# OPTICS.net
KiCad netlist of a schematic drawn in Altium Designer
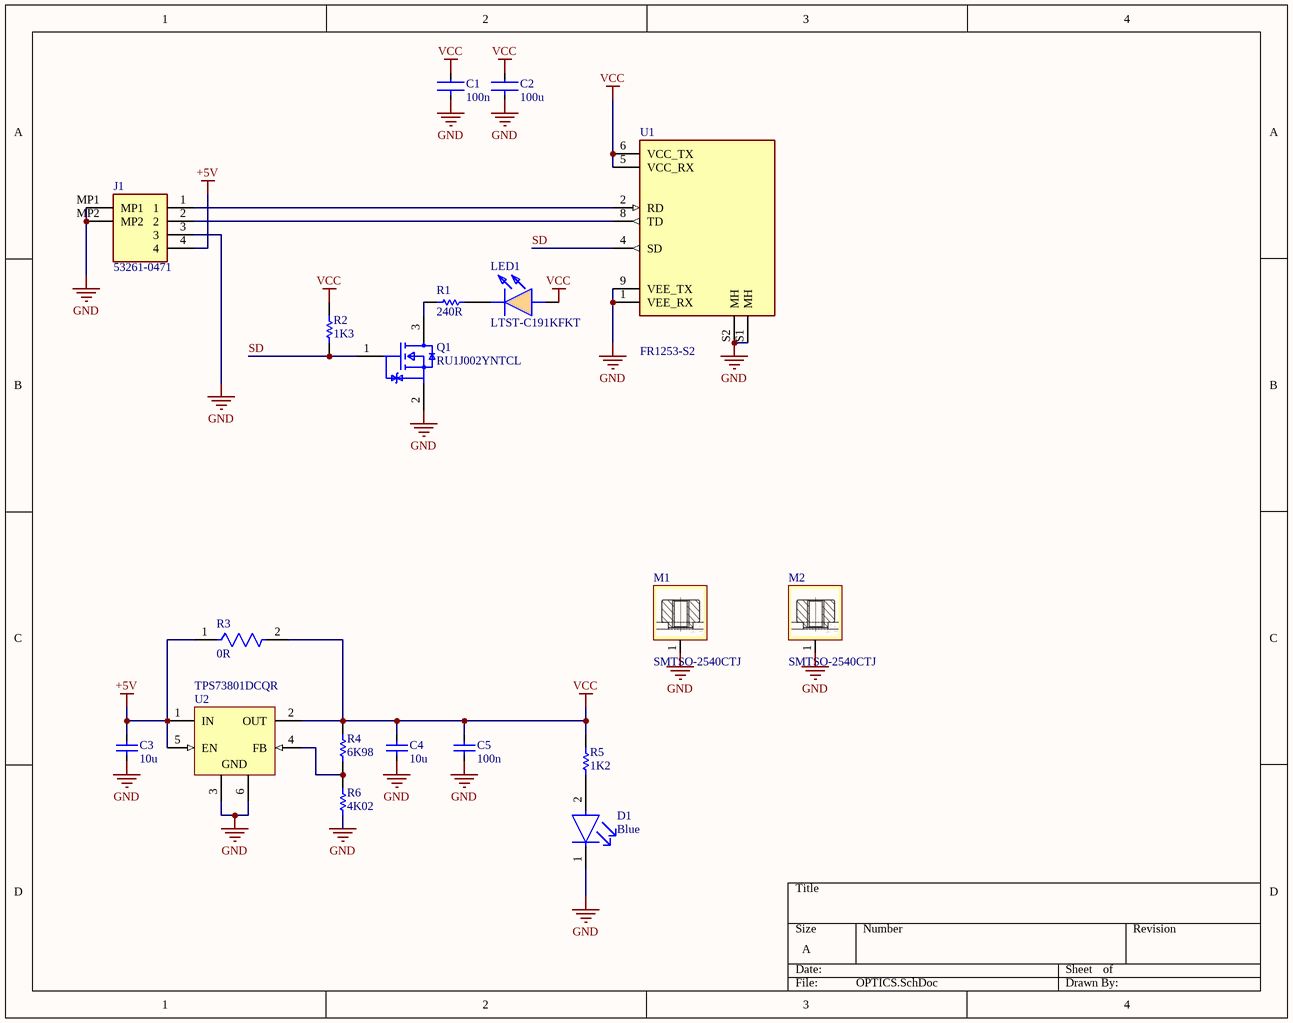
[diagram p0: OPTICS.SchDoc]

(export (version "E")
  (design (tool "Eeschema 10.0.6"))
  (components
    (comp (ref "C1")
      (value "100n")
      (footprint "FP-C1005-050-0_05-IPC_B")
      (description "Multilayer Ceramic Capacitors 100nF ±10% 50V X7R SMD 0402")
      (fields (field (name "VOLTAGE") "50V") (field (name "TOLERANCE") "10%"))
      (libsource (lib "Altium Content Vault") (part "b4654b650e69147ec39a6b967a45e02"))
    )
    (comp (ref "C2")
      (value "100u")
      (footprint "FP-C3216-160-0_3-IPC_B")
      (description "Multilayer Ceramic Capacitors 100uF ±20% 4V X5R SMD 1206")
      (fields (field (name "TOLERANCE") "20%") (field (name "PART NUMBER") "C3216X5R0G107M160AB"))
      (libsource (lib "Altium Content Vault") (part "02cd4be3c70576c341d710602a673aa"))
    )
    (comp (ref "C3")
      (value "10u")
      (footprint "FP-C1608-080-0_1-IPC_C")
      (description "MLCC 10μF ±10% 6.3V JB SMD 0603")
      (fields (field (name "TOLERANCE") "10%") (field (name "Comment") "C1608JB0J106K080AB"))
      (libsource (lib "Schlib1") (part "C1608JB0J106K080AB"))
    )
    (comp (ref "C4")
      (value "10u")
      (footprint "FP-C1608-080-0_1-IPC_C")
      (description "MLCC 10μF ±10% 6.3V JB SMD 0603")
      (fields (field (name "TOLERANCE") "10%") (field (name "Comment") "C1608JB0J106K080AB"))
      (libsource (lib "Schlib1") (part "C1608JB0J106K080AB"))
    )
    (comp (ref "C5")
      (value "100n")
      (footprint "FP-C1005-050-0_05-IPC_C")
      (description "MLCC 100nF ±10% 50V X7R SMD 0402")
      (fields (field (name "VOLTAGE") "50V") (field (name "TOLERANCE") "10%"))
      (libsource (lib "Schlib1") (part "C1005X7R1H104K050BB"))
    )
    (comp (ref "D1")
      (value "LTST-C191TBKT")
      (footprint "FP-LTST-C191TBKT-MFG")
      (description "LED BLUE CLEAR CHIP SMD")
      (fields (field (name "COLOR") "Blue"))
      (libsource (lib "Altium Content Vault") (part "8706943c75ba83719d021d2fdc84c58"))
    )
    (comp (ref "J1")
      (value "53261-0471")
      (footprint "SamacSys:53261-0471")
      (description "Connector")
      (fields (field (name "MOUSER PART NUMBER") "538-53261-0471"))
      (libsource (lib "SamacSys") (part "53261-0471"))
    )
    (comp (ref "LED1")
      (value "LTST-C191KFKT")
      (footprint "SamacSys:LEDC1608X55N")
      (description "LED")
      (fields (field (name "MOUSER PART NUMBER") "859-LTST-C191KFKT") (field (name "MANUFACTURER") "Lite-On"))
      (libsource (lib "SamacSys") (part "LTST-C191KFKT"))
    )
    (comp (ref "M1")
      (value "SMTSO-2540CTJ")
      (footprint "SMTSO-2540CTJ")
      (libsource (lib "Schlib1") (part "SMTSO-2540CTJ"))
    )
    (comp (ref "M2")
      (value "SMTSO-2540CTJ")
      (footprint "SMTSO-2540CTJ")
      (libsource (lib "Schlib1") (part "SMTSO-2540CTJ"))
    )
    (comp (ref "Q1")
      (value "RU1J002YNTCL")
      (footprint "FP-UMT3F-MFG")
      (description "MOSFET N-CH 50V 0.2A UMT3F")
      (fields
        (field (name "MANUFACTURER") "Rohm")
        (field (name "OCTOPART") "https://octopart.com/ru1j002yntcl-rohm-47197697")
      )
      (libsource (lib "Schlib1") (part "RU1J002YNTCL"))
    )
    (comp (ref "R1")
      (value "240R")
      (footprint "RESC0402(1005)_M")
      (description "240R 0.063W 1% 0402 (1005 Metric)  SMD")
      (fields (field (name "POWER") "0.063 W") (field (name "TOLERANCE") "1 %"))
      (libsource (lib "Altium Content Vault") (part "RES"))
    )
    (comp (ref "R2")
      (value "1K3")
      (footprint "RESC1005X40X25ML05T10")
      (fields (field (name "MANUFACTURER") "Yageo / Phycomp") (field (name "PART NUMBER") "RC0402FR-071K3L"))
      (libsource (lib "Altium Content Vault") (part "RES"))
    )
    (comp (ref "R3")
      (value "0R")
      (footprint "FP-RC0402-0_4-IPC_C")
      (description "RES SMD 0 OHM JUMPER 1/16W 0402")
      (fields (field (name "TOLERANCE") "1%") (field (name "Comment") "RC0402FR-070RL"))
      (libsource (lib "Altium Content Vault") (part "1029c3af85768c4190bb7ad29bc67b5"))
    )
    (comp (ref "R4")
      (value "6K98")
      (footprint "RESC1005X40X25ML05T10")
      (fields (field (name "MANUFACTURER") "Yageo / Phycomp") (field (name "PART NUMBER") "RC0402FR-076K98L"))
      (libsource (lib "Altium Content Vault") (part "RES"))
    )
    (comp (ref "R5")
      (value "1K2")
      (footprint "RESC1005X40X25ML05T10")
      (fields (field (name "PART NUMBER") "RC0402FR-071K2L") (field (name "MANUFACTURER") "Yageo / Phycomp"))
      (libsource (lib "Altium Content Vault") (part "RES"))
    )
    (comp (ref "R6")
      (value "4K02")
      (footprint "RESC1005X40X25ML05T10")
      (fields (field (name "MANUFACTURER") "Yageo / Phycomp") (field (name "PART NUMBER") "RC0402FR-074K02L"))
      (libsource (lib "Altium Content Vault") (part "RES"))
    )
    (comp (ref "U1")
      (value "FR1253-S2")
      (footprint "XCVR_AFBR-5803Z")
      (description "Fiber Optic Transceiver Module General Purpose 100Mbps 1300nm 3.3V, 5V SC Through Hole")
      (fields (field (name "MP") "AFBR-5803Z") (field (name "DIGI-KEY_PART_NUMBER") "516-1991-ND"))
      (libsource (lib "Schlib1") (part "FR12XX"))
    )
    (comp (ref "U2")
      (value "TPS73801DCQR")
      (footprint "DCQ0006A_L")
      (fields (field (name "MANUFACTURER") "Texas Instruments"))
      (libsource (lib "Altium Content Vault") (part "TI-TPS73X01-DCQ6"))
    )
  )
  (nets
    (net (code "1") (name "+5V") (class "Default")
      (node (ref "C3") (pin "1") (pinfunction "1_1") (pintype "passive"))
      (node (ref "J1") (pin "4") (pinfunction "4_4") (pintype "passive"))
      (node (ref "R3") (pin "1") (pinfunction "1_1") (pintype "passive"))
      (node (ref "U2") (pin "1") (pinfunction "IN_1") (pintype "power_in"))
      (node (ref "U2") (pin "5") (pinfunction "EN_5") (pintype "input"))
    )
    (net (code "2") (name "/SD") (class "Default")
      (node (ref "Q1") (pin "1") (pinfunction "G_1") (pintype "passive"))
      (node (ref "R2") (pin "1") (pinfunction "1_1") (pintype "passive"))
      (node (ref "U1") (pin "4") (pinfunction "SD_4") (pintype "output"))
    )
    (net (code "3") (name "GND") (class "Default")
      (node (ref "C1") (pin "1") (pinfunction "1_1") (pintype "passive"))
      (node (ref "C2") (pin "1") (pinfunction "1_1") (pintype "passive"))
      (node (ref "C3") (pin "2") (pinfunction "2_2") (pintype "passive"))
      (node (ref "C4") (pin "2") (pinfunction "2_2") (pintype "passive"))
      (node (ref "C5") (pin "2") (pinfunction "2_2") (pintype "passive"))
      (node (ref "D1") (pin "1") (pinfunction "C_1") (pintype "passive"))
      (node (ref "J1") (pin "3") (pinfunction "3_3") (pintype "passive"))
      (node (ref "J1") (pin "MP1") (pinfunction "MP1_MP1") (pintype "passive"))
      (node (ref "J1") (pin "MP2") (pinfunction "MP2_MP2") (pintype "passive"))
      (node (ref "M1") (pin "1") (pinfunction "1_1") (pintype "passive"))
      (node (ref "M2") (pin "1") (pinfunction "1_1") (pintype "passive"))
      (node (ref "Q1") (pin "2") (pinfunction "S_2") (pintype "passive"))
      (node (ref "R6") (pin "1") (pinfunction "1_1") (pintype "passive"))
      (node (ref "U1") (pin "1") (pinfunction "VEE_RX_1") (pintype "power_in"))
      (node (ref "U1") (pin "9") (pinfunction "VEE_TX_9") (pintype "power_in"))
      (node (ref "U1") (pin "S1") (pinfunction "MH_S1") (pintype "passive"))
      (node (ref "U1") (pin "S2") (pinfunction "MH_S2") (pintype "passive"))
      (node (ref "U2") (pin "3") (pinfunction "GND_3") (pintype "power_in"))
      (node (ref "U2") (pin "6") (pinfunction "GND_6") (pintype "power_in"))
    )
    (net (code "4") (name "Net-(D1-A)") (class "Default")
      (node (ref "D1") (pin "2") (pinfunction "A_2") (pintype "passive"))
      (node (ref "R5") (pin "2") (pinfunction "2_2") (pintype "passive"))
    )
    (net (code "5") (name "Net-(LED1-K)") (class "Default")
      (node (ref "LED1") (pin "1") (pinfunction "K_1") (pintype "passive"))
      (node (ref "R1") (pin "1") (pinfunction "1_1") (pintype "passive"))
    )
    (net (code "6") (name "Net-(Q1-D)") (class "Default")
      (node (ref "Q1") (pin "3") (pinfunction "D_3") (pintype "passive"))
      (node (ref "R1") (pin "2") (pinfunction "2_2") (pintype "passive"))
    )
    (net (code "7") (name "Net-(U1-RD)") (class "Default")
      (node (ref "J1") (pin "1") (pinfunction "1_1") (pintype "passive"))
      (node (ref "U1") (pin "2") (pinfunction "RD_2") (pintype "input"))
    )
    (net (code "8") (name "Net-(U1-TD)") (class "Default")
      (node (ref "J1") (pin "2") (pinfunction "2_2") (pintype "passive"))
      (node (ref "U1") (pin "8") (pinfunction "TD_8") (pintype "output"))
    )
    (net (code "9") (name "Net-(U2-FB)") (class "Default")
      (node (ref "R4") (pin "1") (pinfunction "1_1") (pintype "passive"))
      (node (ref "R6") (pin "2") (pinfunction "2_2") (pintype "passive"))
      (node (ref "U2") (pin "4") (pinfunction "FB_4") (pintype "input"))
    )
    (net (code "10") (name "VCC") (class "Default")
      (node (ref "C1") (pin "2") (pinfunction "2_2") (pintype "passive"))
      (node (ref "C2") (pin "2") (pinfunction "2_2") (pintype "passive"))
      (node (ref "C4") (pin "1") (pinfunction "1_1") (pintype "passive"))
      (node (ref "C5") (pin "1") (pinfunction "1_1") (pintype "passive"))
      (node (ref "LED1") (pin "2") (pinfunction "A_2") (pintype "passive"))
      (node (ref "R2") (pin "2") (pinfunction "2_2") (pintype "passive"))
      (node (ref "R3") (pin "2") (pinfunction "2_2") (pintype "passive"))
      (node (ref "R4") (pin "2") (pinfunction "2_2") (pintype "passive"))
      (node (ref "R5") (pin "1") (pinfunction "1_1") (pintype "passive"))
      (node (ref "U1") (pin "5") (pinfunction "VCC_RX_5") (pintype "power_in"))
      (node (ref "U1") (pin "6") (pinfunction "VCC_TX_6") (pintype "power_in"))
      (node (ref "U2") (pin "2") (pinfunction "OUT_2") (pintype "power_in"))
    )
  )
)
